# M452X.net
KiCad netlist of a schematic drawn in EAGLE
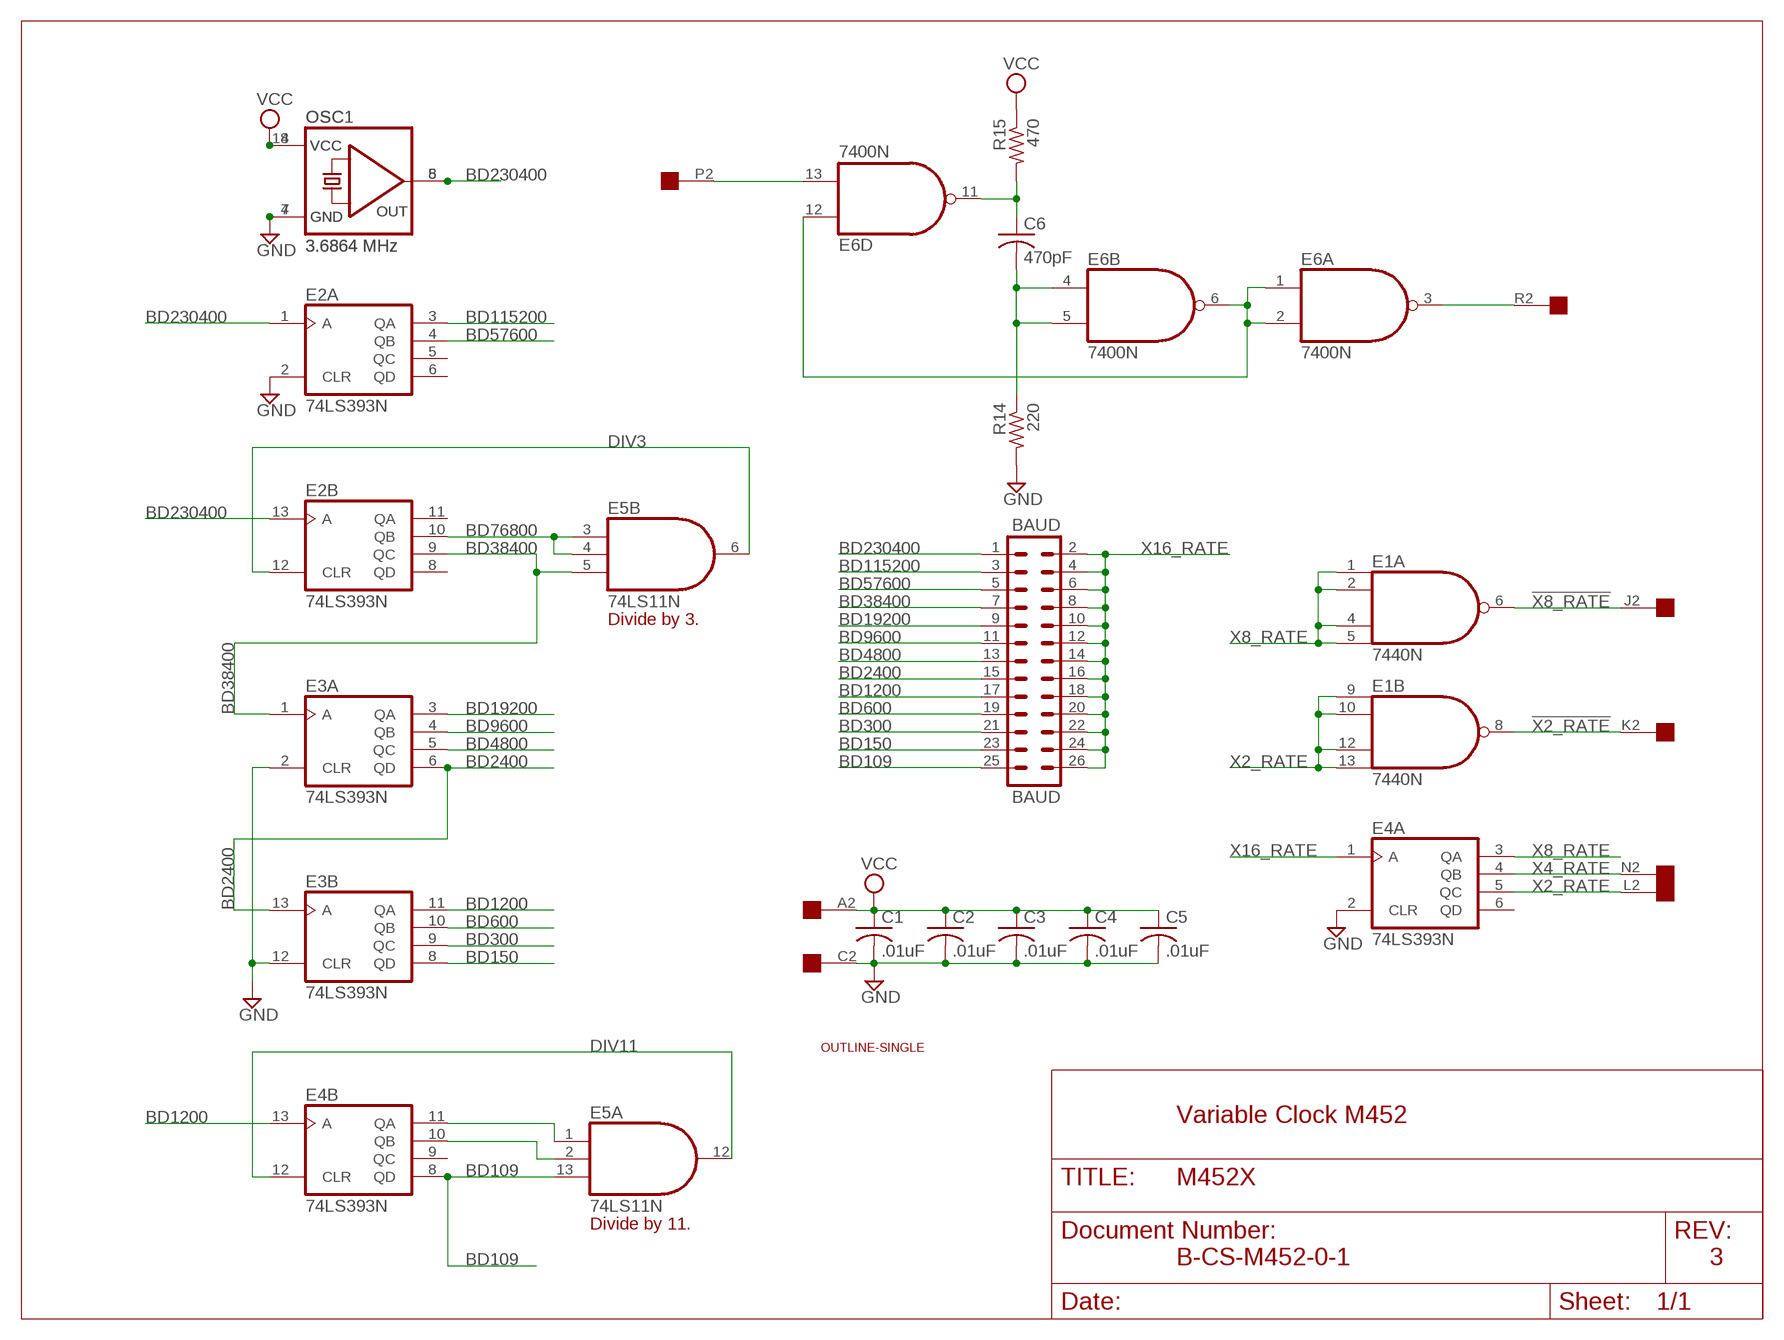
[diagram p0: schematic, sheet 1]

(export (version "E")
  (design (tool "Eeschema 10.0.6"))
  (components
    (comp (ref "BAUD")
      (value "BAUD")
      (footprint "eagle-import:MA13-2")
      (libsource (lib "eagle-import") (part "MA13-2"))
    )
    (comp (ref "C1")
      (value ".01uF")
      (footprint "eagle-import:C050-025X075")
      (libsource (lib "eagle-import") (part "C-US050-025X075"))
    )
    (comp (ref "C2")
      (value ".01uF")
      (footprint "eagle-import:C050-025X075")
      (libsource (lib "eagle-import") (part "C-US050-025X075"))
    )
    (comp (ref "C3")
      (value ".01uF")
      (footprint "eagle-import:C050-025X075")
      (libsource (lib "eagle-import") (part "C-US050-025X075"))
    )
    (comp (ref "C4")
      (value ".01uF")
      (footprint "eagle-import:C050-025X075")
      (libsource (lib "eagle-import") (part "C-US050-025X075"))
    )
    (comp (ref "C5")
      (value ".01uF")
      (footprint "eagle-import:C050-025X075")
      (libsource (lib "eagle-import") (part "C-US050-025X075"))
    )
    (comp (ref "C6")
      (value "470pF")
      (footprint "eagle-import:C075-032X103")
      (libsource (lib "eagle-import") (part "C-US075-032X103"))
    )
    (comp (ref "E1")
      (value "7440N")
      (footprint "eagle-import:DIL14")
      (libsource (lib "eagle-import") (part "7420NS"))
    )
    (comp (ref "E2")
      (value "74LS393N")
      (footprint "eagle-import:DIL14")
      (libsource (lib "eagle-import") (part "74393NLS"))
    )
    (comp (ref "E3")
      (value "74LS393N")
      (footprint "eagle-import:DIL14")
      (libsource (lib "eagle-import") (part "74393NLS"))
    )
    (comp (ref "E4")
      (value "74LS393N")
      (footprint "eagle-import:DIL14")
      (libsource (lib "eagle-import") (part "74393NLS"))
    )
    (comp (ref "E5")
      (value "74LS11N")
      (footprint "eagle-import:DIL14")
      (libsource (lib "eagle-import") (part "7411NLS"))
    )
    (comp (ref "E6")
      (value "7400N")
      (footprint "eagle-import:DIL14")
      (libsource (lib "eagle-import") (part "7400NLS"))
    )
    (comp (ref "OSC")
      (value "3.6864 MHz")
      (footprint "eagle-import:DIL08S")
      (libsource (lib "eagle-import") (part "QG5460"))
    )
    (comp (ref "OSC1")
      (value "3.6864 MHz")
      (footprint "eagle-import:DIL14S")
      (libsource (lib "eagle-import") (part "QG5860"))
    )
    (comp (ref "R14")
      (value "220")
      (footprint "eagle-import:0207_10")
      (libsource (lib "eagle-import") (part "R-US_0207/10"))
    )
    (comp (ref "R15")
      (value "470")
      (footprint "eagle-import:0207_10")
      (libsource (lib "eagle-import") (part "R-US_0207/10"))
    )
    (comp (ref "U$1")
      (value "OUTLINE-SINGLE")
      (footprint "eagle-import:SINGLE")
      (libsource (lib "eagle-import") (part "OUTLINE-SINGLE"))
    )
    (comp (ref "U$2")
      (value "EDGE-1")
      (footprint "eagle-import:EDGE-CON1")
      (libsource (lib "eagle-import") (part "EDGE-1"))
    )
  )
  (nets
    (net (code "1") (name "/BD109") (class "Default")
      (node (ref "BAUD") (pin "25") (pinfunction "25_25") (pintype "passive"))
      (node (ref "E4") (pin "8") (pinfunction "QD_8") (pintype "output"))
      (node (ref "E5") (pin "13") (pinfunction "I2_13") (pintype "input"))
    )
    (net (code "2") (name "/BD150") (class "Default")
      (node (ref "BAUD") (pin "23") (pinfunction "23_23") (pintype "passive"))
      (node (ref "E3") (pin "8") (pinfunction "QD_8") (pintype "output"))
    )
    (net (code "3") (name "/BD300") (class "Default")
      (node (ref "BAUD") (pin "21") (pinfunction "21_21") (pintype "passive"))
      (node (ref "E3") (pin "9") (pinfunction "QC_9") (pintype "output"))
    )
    (net (code "4") (name "/BD600") (class "Default")
      (node (ref "BAUD") (pin "19") (pinfunction "19_19") (pintype "passive"))
      (node (ref "E3") (pin "10") (pinfunction "QB_10") (pintype "output"))
    )
    (net (code "5") (name "/BD1200") (class "Default")
      (node (ref "BAUD") (pin "17") (pinfunction "17_17") (pintype "passive"))
      (node (ref "E3") (pin "11") (pinfunction "QA_11") (pintype "output"))
      (node (ref "E4") (pin "13") (pinfunction "A_13") (pintype "input"))
    )
    (net (code "6") (name "/BD2400") (class "Default")
      (node (ref "BAUD") (pin "15") (pinfunction "15_15") (pintype "passive"))
      (node (ref "E3") (pin "13") (pinfunction "A_13") (pintype "input"))
      (node (ref "E3") (pin "6") (pinfunction "QD_6") (pintype "output"))
    )
    (net (code "7") (name "/BD4800") (class "Default")
      (node (ref "BAUD") (pin "13") (pinfunction "13_13") (pintype "passive"))
      (node (ref "E3") (pin "5") (pinfunction "QC_5") (pintype "output"))
    )
    (net (code "8") (name "/BD9600") (class "Default")
      (node (ref "BAUD") (pin "11") (pinfunction "11_11") (pintype "passive"))
      (node (ref "E3") (pin "4") (pinfunction "QB_4") (pintype "output"))
    )
    (net (code "9") (name "/BD19200") (class "Default")
      (node (ref "BAUD") (pin "9") (pinfunction "9_9") (pintype "passive"))
      (node (ref "E3") (pin "3") (pinfunction "QA_3") (pintype "output"))
    )
    (net (code "10") (name "/BD38400") (class "Default")
      (node (ref "BAUD") (pin "7") (pinfunction "7_7") (pintype "passive"))
      (node (ref "E2") (pin "9") (pinfunction "QC_9") (pintype "output"))
      (node (ref "E3") (pin "1") (pinfunction "A_1") (pintype "input"))
      (node (ref "E5") (pin "5") (pinfunction "I2_5") (pintype "input"))
    )
    (net (code "11") (name "/BD57600") (class "Default")
      (node (ref "BAUD") (pin "5") (pinfunction "5_5") (pintype "passive"))
      (node (ref "E2") (pin "4") (pinfunction "QB_4") (pintype "output"))
    )
    (net (code "12") (name "/BD76800") (class "Default")
      (node (ref "E2") (pin "10") (pinfunction "QB_10") (pintype "output"))
      (node (ref "E5") (pin "3") (pinfunction "I0_3") (pintype "input"))
      (node (ref "E5") (pin "4") (pinfunction "I1_4") (pintype "input"))
    )
    (net (code "13") (name "/BD115200") (class "Default")
      (node (ref "BAUD") (pin "3") (pinfunction "3_3") (pintype "passive"))
      (node (ref "E2") (pin "3") (pinfunction "QA_3") (pintype "output"))
    )
    (net (code "14") (name "/BD230400") (class "Default")
      (node (ref "BAUD") (pin "1") (pinfunction "1_1") (pintype "passive"))
      (node (ref "E2") (pin "1") (pinfunction "A_1") (pintype "input"))
      (node (ref "E2") (pin "13") (pinfunction "A_13") (pintype "input"))
      (node (ref "OSC") (pin "5") (pinfunction "OUT_5") (pintype "output"))
      (node (ref "OSC1") (pin "8") (pinfunction "OUT_8") (pintype "output"))
    )
    (net (code "15") (name "/DIV3") (class "Default")
      (node (ref "E2") (pin "12") (pinfunction "CLR_12") (pintype "input"))
      (node (ref "E5") (pin "6") (pinfunction "O_6") (pintype "output"))
    )
    (net (code "16") (name "/DIV11") (class "Default")
      (node (ref "E4") (pin "12") (pinfunction "CLR_12") (pintype "input"))
      (node (ref "E5") (pin "12") (pinfunction "O_12") (pintype "output"))
    )
    (net (code "17") (name "/X2_RATE") (class "Default")
      (node (ref "E1") (pin "10") (pinfunction "I1_10") (pintype "input"))
      (node (ref "E1") (pin "12") (pinfunction "I2_12") (pintype "input"))
      (node (ref "E1") (pin "13") (pinfunction "I3_13") (pintype "input"))
      (node (ref "E1") (pin "9") (pinfunction "I0_9") (pintype "input"))
      (node (ref "E4") (pin "5") (pinfunction "QC_5") (pintype "output"))
      (node (ref "U$2") (pin "L2") (pinfunction "1_L2") (pintype "bidirectional"))
    )
    (net (code "18") (name "/X4_RATE") (class "Default")
      (node (ref "E4") (pin "4") (pinfunction "QB_4") (pintype "output"))
      (node (ref "U$2") (pin "N2") (pinfunction "1_N2") (pintype "bidirectional"))
    )
    (net (code "19") (name "/X8_RATE") (class "Default")
      (node (ref "E1") (pin "1") (pinfunction "I0_1") (pintype "input"))
      (node (ref "E1") (pin "2") (pinfunction "I1_2") (pintype "input"))
      (node (ref "E1") (pin "4") (pinfunction "I2_4") (pintype "input"))
      (node (ref "E1") (pin "5") (pinfunction "I3_5") (pintype "input"))
      (node (ref "E4") (pin "3") (pinfunction "QA_3") (pintype "output"))
    )
    (net (code "20") (name "/X16_RATE") (class "Default")
      (node (ref "BAUD") (pin "10") (pinfunction "10_10") (pintype "passive"))
      (node (ref "BAUD") (pin "12") (pinfunction "12_12") (pintype "passive"))
      (node (ref "BAUD") (pin "14") (pinfunction "14_14") (pintype "passive"))
      (node (ref "BAUD") (pin "16") (pinfunction "16_16") (pintype "passive"))
      (node (ref "BAUD") (pin "18") (pinfunction "18_18") (pintype "passive"))
      (node (ref "BAUD") (pin "2") (pinfunction "2_2") (pintype "passive"))
      (node (ref "BAUD") (pin "20") (pinfunction "20_20") (pintype "passive"))
      (node (ref "BAUD") (pin "22") (pinfunction "22_22") (pintype "passive"))
      (node (ref "BAUD") (pin "24") (pinfunction "24_24") (pintype "passive"))
      (node (ref "BAUD") (pin "26") (pinfunction "26_26") (pintype "passive"))
      (node (ref "BAUD") (pin "4") (pinfunction "4_4") (pintype "passive"))
      (node (ref "BAUD") (pin "6") (pinfunction "6_6") (pintype "passive"))
      (node (ref "BAUD") (pin "8") (pinfunction "8_8") (pintype "passive"))
      (node (ref "E4") (pin "1") (pinfunction "A_1") (pintype "input"))
    )
    (net (code "21") (name "/~{X2_RATE}") (class "Default")
      (node (ref "E1") (pin "8") (pinfunction "O_8") (pintype "output"))
      (node (ref "U$2") (pin "K2") (pinfunction "1_K2") (pintype "bidirectional"))
    )
    (net (code "22") (name "/~{X8_RATE}") (class "Default")
      (node (ref "E1") (pin "6") (pinfunction "O_6") (pintype "output"))
      (node (ref "U$2") (pin "J2") (pinfunction "1_J2") (pintype "bidirectional"))
    )
    (net (code "23") (name "GND") (class "Default")
      (node (ref "C1") (pin "2") (pinfunction "2_2") (pintype "passive"))
      (node (ref "C2") (pin "2") (pinfunction "2_2") (pintype "passive"))
      (node (ref "C3") (pin "2") (pinfunction "2_2") (pintype "passive"))
      (node (ref "C4") (pin "2") (pinfunction "2_2") (pintype "passive"))
      (node (ref "C5") (pin "2") (pinfunction "2_2") (pintype "passive"))
      (node (ref "E2") (pin "2") (pinfunction "CLR_2") (pintype "input"))
      (node (ref "E3") (pin "12") (pinfunction "CLR_12") (pintype "input"))
      (node (ref "E3") (pin "2") (pinfunction "CLR_2") (pintype "input"))
      (node (ref "E4") (pin "2") (pinfunction "CLR_2") (pintype "input"))
      (node (ref "OSC") (pin "4") (pinfunction "GND_4") (pintype "power_in"))
      (node (ref "OSC1") (pin "7") (pinfunction "GND_7") (pintype "power_in"))
      (node (ref "R14") (pin "2") (pinfunction "2_2") (pintype "passive"))
      (node (ref "U$2") (pin "C2") (pinfunction "1_C2") (pintype "bidirectional"))
    )
    (net (code "24") (name "Net-(E4B-QA)") (class "Default")
      (node (ref "E4") (pin "11") (pinfunction "QA_11") (pintype "output"))
      (node (ref "E5") (pin "1") (pinfunction "I0_1") (pintype "input"))
    )
    (net (code "25") (name "Net-(E4B-QB)") (class "Default")
      (node (ref "E4") (pin "10") (pinfunction "QB_10") (pintype "output"))
      (node (ref "E5") (pin "2") (pinfunction "I1_2") (pintype "input"))
    )
    (net (code "26") (name "Net-(E6A-I0)") (class "Default")
      (node (ref "E6") (pin "1") (pinfunction "I0_1") (pintype "input"))
      (node (ref "E6") (pin "12") (pinfunction "I0_12") (pintype "input"))
      (node (ref "E6") (pin "2") (pinfunction "I1_2") (pintype "input"))
      (node (ref "E6") (pin "6") (pinfunction "O_6") (pintype "output"))
    )
    (net (code "27") (name "Net-(E6A-O)") (class "Default")
      (node (ref "E6") (pin "3") (pinfunction "O_3") (pintype "output"))
      (node (ref "U$2") (pin "R2") (pinfunction "1_R2") (pintype "bidirectional"))
    )
    (net (code "28") (name "Net-(E6B-I0)") (class "Default")
      (node (ref "C6") (pin "2") (pinfunction "2_2") (pintype "passive"))
      (node (ref "E6") (pin "4") (pinfunction "I0_4") (pintype "input"))
      (node (ref "E6") (pin "5") (pinfunction "I1_5") (pintype "input"))
      (node (ref "R14") (pin "1") (pinfunction "1_1") (pintype "passive"))
    )
    (net (code "29") (name "Net-(E6D-I1)") (class "Default")
      (node (ref "E6") (pin "13") (pinfunction "I1_13") (pintype "input"))
      (node (ref "U$2") (pin "P2") (pinfunction "1_P2") (pintype "bidirectional"))
    )
    (net (code "30") (name "Net-(E6D-O)") (class "Default")
      (node (ref "C6") (pin "1") (pinfunction "1_1") (pintype "passive"))
      (node (ref "E6") (pin "11") (pinfunction "O_11") (pintype "output"))
      (node (ref "R15") (pin "2") (pinfunction "2_2") (pintype "passive"))
    )
    (net (code "31") (name "VCC") (class "Default")
      (node (ref "C1") (pin "1") (pinfunction "1_1") (pintype "passive"))
      (node (ref "C2") (pin "1") (pinfunction "1_1") (pintype "passive"))
      (node (ref "C3") (pin "1") (pinfunction "1_1") (pintype "passive"))
      (node (ref "C4") (pin "1") (pinfunction "1_1") (pintype "passive"))
      (node (ref "C5") (pin "1") (pinfunction "1_1") (pintype "passive"))
      (node (ref "OSC") (pin "8") (pinfunction "VCC_8") (pintype "power_in"))
      (node (ref "OSC1") (pin "14") (pinfunction "VCC_14") (pintype "power_in"))
      (node (ref "R15") (pin "1") (pinfunction "1_1") (pintype "passive"))
      (node (ref "U$2") (pin "A2") (pinfunction "1_A2") (pintype "bidirectional"))
    )
    (net (code "32") (name "unconnected-(E2A-QC-Pad5)") (class "Default")
      (node (ref "E2") (pin "5") (pinfunction "QC_5") (pintype "output"))
    )
    (net (code "33") (name "unconnected-(E2A-QD-Pad6)") (class "Default")
      (node (ref "E2") (pin "6") (pinfunction "QD_6") (pintype "output"))
    )
    (net (code "34") (name "unconnected-(E2B-QA-Pad11)") (class "Default")
      (node (ref "E2") (pin "11") (pinfunction "QA_11") (pintype "output"))
    )
    (net (code "35") (name "unconnected-(E2B-QD-Pad8)") (class "Default")
      (node (ref "E2") (pin "8") (pinfunction "QD_8") (pintype "output"))
    )
    (net (code "36") (name "unconnected-(E4A-QD-Pad6)") (class "Default")
      (node (ref "E4") (pin "6") (pinfunction "QD_6") (pintype "output"))
    )
    (net (code "37") (name "unconnected-(E4B-QC-Pad9)") (class "Default")
      (node (ref "E4") (pin "9") (pinfunction "QC_9") (pintype "output"))
    )
  )
)
